# Cell_Voltage_Sensing.net
KiCad netlist of a schematic drawn in Altium Designer
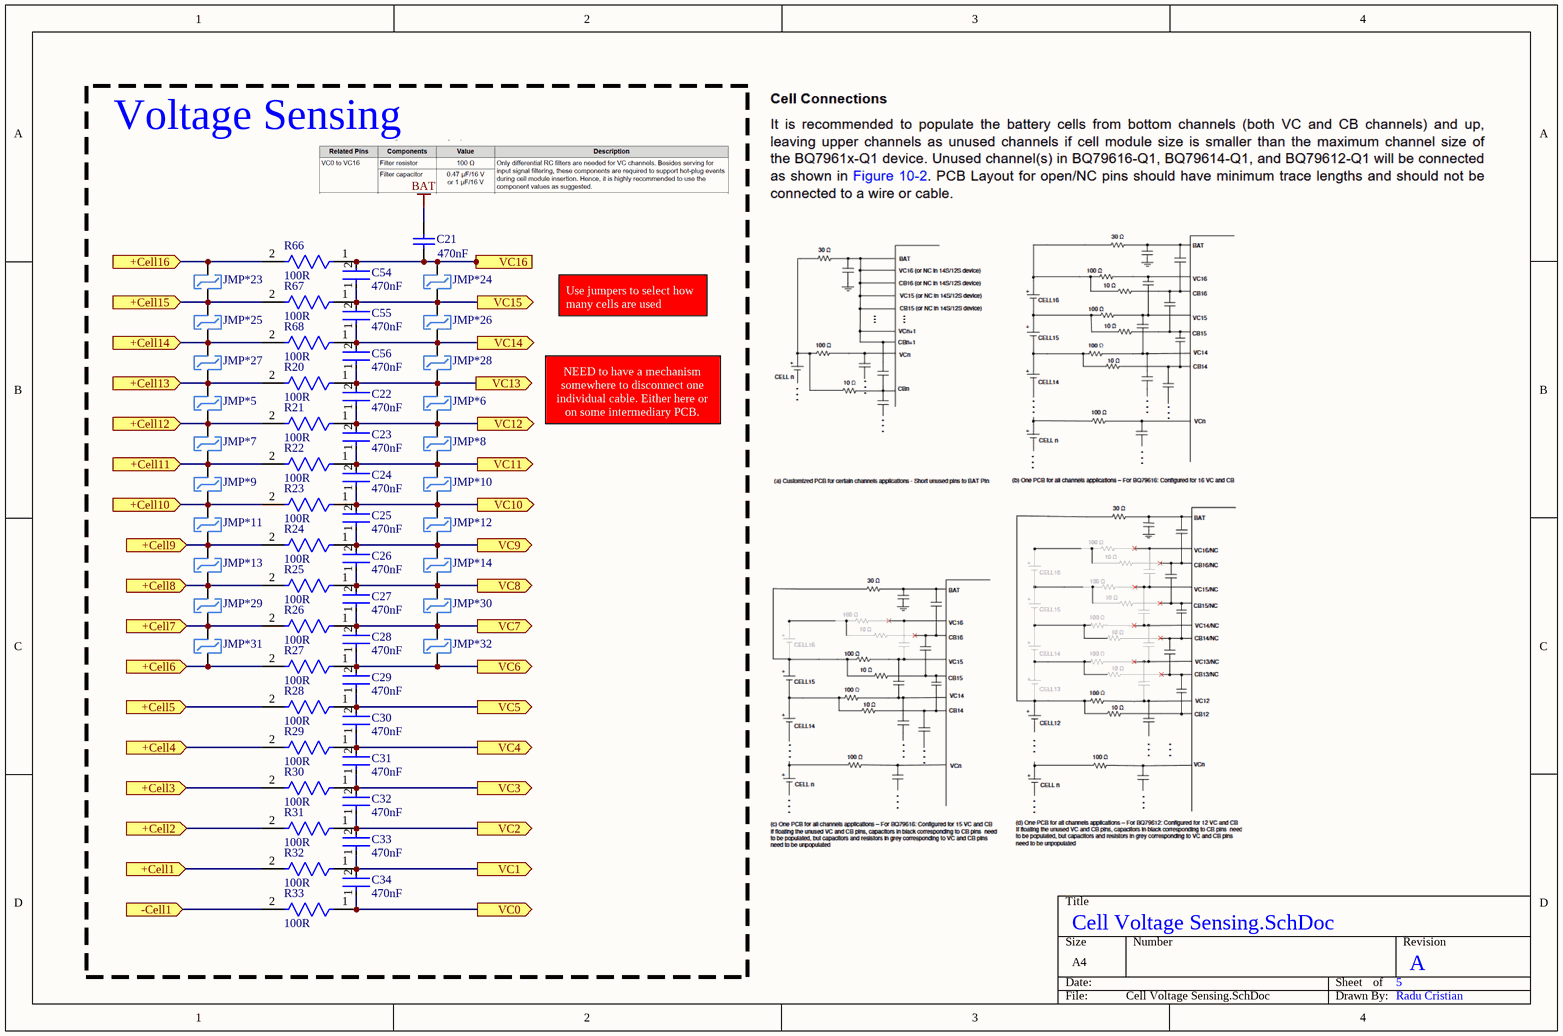
[diagram p0: Cell Voltage Sensing.SchDoc]

(export (version "E")
  (design (tool "Eeschema 10.0.6"))
  (components
    (comp (ref "C21")
      (value "470nF")
      (footprint "CAPC0603(1608)100_N")
      (description "CAP 470nF 25V ±20% 0603 (1608 Metric) Thickness 1mm SMD")
      (fields (field (name "TOLERANCE") "Â±20%") (field (name "Comment") "CAP 470nF 25V 0603(1608)"))
      (libsource (lib "Altium Content Vault") (part "CAP"))
    )
    (comp (ref "C22")
      (value "08055C474J4Z2A")
      (footprint "FP-0805-L_2_01_0_2-W_1_25-IPC_C")
      (description "Automotive Ceramic Capacitor, 0805, 470nF, 5%, X7R, 15%, 50V")
      (fields (field (name "CAPACITANCE") "470nF") (field (name "TOLERANCE") "5%"))
      (libsource (lib "Altium Content Vault") (part "b4654b650e69147ec39a6b967a45e02"))
    )
    (comp (ref "C23")
      (value "08055C474J4Z2A")
      (footprint "FP-0805-L_2_01_0_2-W_1_25-IPC_C")
      (description "Automotive Ceramic Capacitor, 0805, 470nF, 5%, X7R, 15%, 50V")
      (fields (field (name "CAPACITANCE") "470nF") (field (name "TOLERANCE") "5%"))
      (libsource (lib "Altium Content Vault") (part "b4654b650e69147ec39a6b967a45e02"))
    )
    (comp (ref "C24")
      (value "08055C474J4Z2A")
      (footprint "FP-0805-L_2_01_0_2-W_1_25-IPC_C")
      (description "Automotive Ceramic Capacitor, 0805, 470nF, 5%, X7R, 15%, 50V")
      (fields (field (name "CAPACITANCE") "470nF") (field (name "TOLERANCE") "5%"))
      (libsource (lib "Altium Content Vault") (part "b4654b650e69147ec39a6b967a45e02"))
    )
    (comp (ref "C25")
      (value "08055C474J4Z2A")
      (footprint "FP-0805-L_2_01_0_2-W_1_25-IPC_C")
      (description "Automotive Ceramic Capacitor, 0805, 470nF, 5%, X7R, 15%, 50V")
      (fields (field (name "CAPACITANCE") "470nF") (field (name "TOLERANCE") "5%"))
      (libsource (lib "Altium Content Vault") (part "b4654b650e69147ec39a6b967a45e02"))
    )
    (comp (ref "C26")
      (value "08055C474J4Z2A")
      (footprint "FP-0805-L_2_01_0_2-W_1_25-IPC_C")
      (description "Automotive Ceramic Capacitor, 0805, 470nF, 5%, X7R, 15%, 50V")
      (fields (field (name "CAPACITANCE") "470nF") (field (name "TOLERANCE") "5%"))
      (libsource (lib "Altium Content Vault") (part "b4654b650e69147ec39a6b967a45e02"))
    )
    (comp (ref "C27")
      (value "08055C474J4Z2A")
      (footprint "FP-0805-L_2_01_0_2-W_1_25-IPC_C")
      (description "Automotive Ceramic Capacitor, 0805, 470nF, 5%, X7R, 15%, 50V")
      (fields (field (name "CAPACITANCE") "470nF") (field (name "TOLERANCE") "5%"))
      (libsource (lib "Altium Content Vault") (part "b4654b650e69147ec39a6b967a45e02"))
    )
    (comp (ref "C28")
      (value "08055C474J4Z2A")
      (footprint "FP-0805-L_2_01_0_2-W_1_25-IPC_C")
      (description "Automotive Ceramic Capacitor, 0805, 470nF, 5%, X7R, 15%, 50V")
      (fields (field (name "CAPACITANCE") "470nF") (field (name "TOLERANCE") "5%"))
      (libsource (lib "Altium Content Vault") (part "b4654b650e69147ec39a6b967a45e02"))
    )
    (comp (ref "C29")
      (value "08055C474J4Z2A")
      (footprint "FP-0805-L_2_01_0_2-W_1_25-IPC_C")
      (description "Automotive Ceramic Capacitor, 0805, 470nF, 5%, X7R, 15%, 50V")
      (fields (field (name "CAPACITANCE") "470nF") (field (name "TOLERANCE") "5%"))
      (libsource (lib "Altium Content Vault") (part "b4654b650e69147ec39a6b967a45e02"))
    )
    (comp (ref "C30")
      (value "08055C474J4Z2A")
      (footprint "FP-0805-L_2_01_0_2-W_1_25-IPC_C")
      (description "Automotive Ceramic Capacitor, 0805, 470nF, 5%, X7R, 15%, 50V")
      (fields (field (name "CAPACITANCE") "470nF") (field (name "TOLERANCE") "5%"))
      (libsource (lib "Altium Content Vault") (part "b4654b650e69147ec39a6b967a45e02"))
    )
    (comp (ref "C31")
      (value "08055C474J4Z2A")
      (footprint "FP-0805-L_2_01_0_2-W_1_25-IPC_C")
      (description "Automotive Ceramic Capacitor, 0805, 470nF, 5%, X7R, 15%, 50V")
      (fields (field (name "CAPACITANCE") "470nF") (field (name "TOLERANCE") "5%"))
      (libsource (lib "Altium Content Vault") (part "b4654b650e69147ec39a6b967a45e02"))
    )
    (comp (ref "C32")
      (value "08055C474J4Z2A")
      (footprint "FP-0805-L_2_01_0_2-W_1_25-IPC_C")
      (description "Automotive Ceramic Capacitor, 0805, 470nF, 5%, X7R, 15%, 50V")
      (fields (field (name "CAPACITANCE") "470nF") (field (name "TOLERANCE") "5%"))
      (libsource (lib "Altium Content Vault") (part "b4654b650e69147ec39a6b967a45e02"))
    )
    (comp (ref "C33")
      (value "08055C474J4Z2A")
      (footprint "FP-0805-L_2_01_0_2-W_1_25-IPC_C")
      (description "Automotive Ceramic Capacitor, 0805, 470nF, 5%, X7R, 15%, 50V")
      (fields (field (name "CAPACITANCE") "470nF") (field (name "TOLERANCE") "5%"))
      (libsource (lib "Altium Content Vault") (part "b4654b650e69147ec39a6b967a45e02"))
    )
    (comp (ref "C34")
      (value "08055C474J4Z2A")
      (footprint "FP-0805-L_2_01_0_2-W_1_25-IPC_C")
      (description "Automotive Ceramic Capacitor, 0805, 470nF, 5%, X7R, 15%, 50V")
      (fields (field (name "CAPACITANCE") "470nF") (field (name "TOLERANCE") "5%"))
      (libsource (lib "Altium Content Vault") (part "b4654b650e69147ec39a6b967a45e02"))
    )
    (comp (ref "C54")
      (value "08055C474J4Z2A")
      (footprint "FP-0805-L_2_01_0_2-W_1_25-IPC_C")
      (description "Automotive Ceramic Capacitor, 0805, 470nF, 5%, X7R, 15%, 50V")
      (fields (field (name "CAPACITANCE") "470nF") (field (name "TOLERANCE") "5%"))
      (libsource (lib "Altium Content Vault") (part "b4654b650e69147ec39a6b967a45e02"))
    )
    (comp (ref "C55")
      (value "08055C474J4Z2A")
      (footprint "FP-0805-L_2_01_0_2-W_1_25-IPC_C")
      (description "Automotive Ceramic Capacitor, 0805, 470nF, 5%, X7R, 15%, 50V")
      (fields (field (name "CAPACITANCE") "470nF") (field (name "TOLERANCE") "5%"))
      (libsource (lib "Altium Content Vault") (part "b4654b650e69147ec39a6b967a45e02"))
    )
    (comp (ref "C56")
      (value "08055C474J4Z2A")
      (footprint "FP-0805-L_2_01_0_2-W_1_25-IPC_C")
      (description "Automotive Ceramic Capacitor, 0805, 470nF, 5%, X7R, 15%, 50V")
      (fields (field (name "CAPACITANCE") "470nF") (field (name "TOLERANCE") "5%"))
      (libsource (lib "Altium Content Vault") (part "b4654b650e69147ec39a6b967a45e02"))
    )
    (comp (ref "JMP*5")
      (value "Solder Jumper")
      (footprint "Solder Jumper-Footprint-1")
      (description "2 port solder jumper")
      (libsource (lib "goulash den") (part "Jumper"))
    )
    (comp (ref "JMP*6")
      (value "Solder Jumper")
      (footprint "Solder Jumper-Footprint-1")
      (description "2 port solder jumper")
      (libsource (lib "goulash den") (part "Jumper"))
    )
    (comp (ref "JMP*7")
      (value "Solder Jumper")
      (footprint "Solder Jumper-Footprint-1")
      (description "2 port solder jumper")
      (libsource (lib "goulash den") (part "Jumper"))
    )
    (comp (ref "JMP*8")
      (value "Solder Jumper")
      (footprint "Solder Jumper-Footprint-1")
      (description "2 port solder jumper")
      (libsource (lib "goulash den") (part "Jumper"))
    )
    (comp (ref "JMP*9")
      (value "Solder Jumper")
      (footprint "Solder Jumper-Footprint-1")
      (description "2 port solder jumper")
      (libsource (lib "goulash den") (part "Jumper"))
    )
    (comp (ref "JMP*10")
      (value "Solder Jumper")
      (footprint "Solder Jumper-Footprint-1")
      (description "2 port solder jumper")
      (libsource (lib "goulash den") (part "Jumper"))
    )
    (comp (ref "JMP*11")
      (value "Solder Jumper")
      (footprint "Solder Jumper-Footprint-1")
      (description "2 port solder jumper")
      (libsource (lib "goulash den") (part "Jumper"))
    )
    (comp (ref "JMP*12")
      (value "Solder Jumper")
      (footprint "Solder Jumper-Footprint-1")
      (description "2 port solder jumper")
      (libsource (lib "goulash den") (part "Jumper"))
    )
    (comp (ref "JMP*13")
      (value "Solder Jumper")
      (footprint "Solder Jumper-Footprint-1")
      (description "2 port solder jumper")
      (libsource (lib "goulash den") (part "Jumper"))
    )
    (comp (ref "JMP*14")
      (value "Solder Jumper")
      (footprint "Solder Jumper-Footprint-1")
      (description "2 port solder jumper")
      (libsource (lib "goulash den") (part "Jumper"))
    )
    (comp (ref "JMP*23")
      (value "Solder Jumper")
      (footprint "Solder Jumper-Footprint-1")
      (description "2 port solder jumper")
      (libsource (lib "goulash den") (part "Jumper"))
    )
    (comp (ref "JMP*24")
      (value "Solder Jumper")
      (footprint "Solder Jumper-Footprint-1")
      (description "2 port solder jumper")
      (libsource (lib "goulash den") (part "Jumper"))
    )
    (comp (ref "JMP*25")
      (value "Solder Jumper")
      (footprint "Solder Jumper-Footprint-1")
      (description "2 port solder jumper")
      (libsource (lib "goulash den") (part "Jumper"))
    )
    (comp (ref "JMP*26")
      (value "Solder Jumper")
      (footprint "Solder Jumper-Footprint-1")
      (description "2 port solder jumper")
      (libsource (lib "goulash den") (part "Jumper"))
    )
    (comp (ref "JMP*27")
      (value "Solder Jumper")
      (footprint "Solder Jumper-Footprint-1")
      (description "2 port solder jumper")
      (libsource (lib "goulash den") (part "Jumper"))
    )
    (comp (ref "JMP*28")
      (value "Solder Jumper")
      (footprint "Solder Jumper-Footprint-1")
      (description "2 port solder jumper")
      (libsource (lib "goulash den") (part "Jumper"))
    )
    (comp (ref "JMP*29")
      (value "Solder Jumper")
      (footprint "Solder Jumper-Footprint-1")
      (description "2 port solder jumper")
      (libsource (lib "goulash den") (part "Jumper"))
    )
    (comp (ref "JMP*30")
      (value "Solder Jumper")
      (footprint "Solder Jumper-Footprint-1")
      (description "2 port solder jumper")
      (libsource (lib "goulash den") (part "Jumper"))
    )
    (comp (ref "JMP*31")
      (value "Solder Jumper")
      (footprint "Solder Jumper-Footprint-1")
      (description "2 port solder jumper")
      (libsource (lib "goulash den") (part "Jumper"))
    )
    (comp (ref "JMP*32")
      (value "Solder Jumper")
      (footprint "Solder Jumper-Footprint-1")
      (description "2 port solder jumper")
      (libsource (lib "goulash den") (part "Jumper"))
    )
    (comp (ref "R20")
      (value "CRCW0603100RFHEAP")
      (footprint "FP-CRCW0603-Pe3-MFG")
      (description "RES Thick Film, 100Ω, 1%, 0.1W, 50ppm/°C, 0603")
      (fields (field (name "RESISTANCE") "100R") (field (name "TOLERANCE") "1%"))
      (libsource (lib "Altium Content Vault") (part "1029c3af85768c4190bb7ad29bc67b5"))
    )
    (comp (ref "R21")
      (value "CRCW0603100RFHEAP")
      (footprint "FP-CRCW0603-Pe3-MFG")
      (description "RES Thick Film, 100Ω, 1%, 0.1W, 50ppm/°C, 0603")
      (fields (field (name "RESISTANCE") "100R") (field (name "TOLERANCE") "1%"))
      (libsource (lib "Altium Content Vault") (part "1029c3af85768c4190bb7ad29bc67b5"))
    )
    (comp (ref "R22")
      (value "CRCW0603100RFHEAP")
      (footprint "FP-CRCW0603-Pe3-MFG")
      (description "RES Thick Film, 100Ω, 1%, 0.1W, 50ppm/°C, 0603")
      (fields (field (name "RESISTANCE") "100R") (field (name "TOLERANCE") "1%"))
      (libsource (lib "Altium Content Vault") (part "1029c3af85768c4190bb7ad29bc67b5"))
    )
    (comp (ref "R23")
      (value "CRCW0603100RFHEAP")
      (footprint "FP-CRCW0603-Pe3-MFG")
      (description "RES Thick Film, 100Ω, 1%, 0.1W, 50ppm/°C, 0603")
      (fields (field (name "RESISTANCE") "100R") (field (name "TOLERANCE") "1%"))
      (libsource (lib "Altium Content Vault") (part "1029c3af85768c4190bb7ad29bc67b5"))
    )
    (comp (ref "R24")
      (value "CRCW0603100RFHEAP")
      (footprint "FP-CRCW0603-Pe3-MFG")
      (description "RES Thick Film, 100Ω, 1%, 0.1W, 50ppm/°C, 0603")
      (fields (field (name "RESISTANCE") "100R") (field (name "TOLERANCE") "1%"))
      (libsource (lib "Altium Content Vault") (part "1029c3af85768c4190bb7ad29bc67b5"))
    )
    (comp (ref "R25")
      (value "CRCW0603100RFHEAP")
      (footprint "FP-CRCW0603-Pe3-MFG")
      (description "RES Thick Film, 100Ω, 1%, 0.1W, 50ppm/°C, 0603")
      (fields (field (name "RESISTANCE") "100R") (field (name "TOLERANCE") "1%"))
      (libsource (lib "Altium Content Vault") (part "1029c3af85768c4190bb7ad29bc67b5"))
    )
    (comp (ref "R26")
      (value "CRCW0603100RFHEAP")
      (footprint "FP-CRCW0603-Pe3-MFG")
      (description "RES Thick Film, 100Ω, 1%, 0.1W, 50ppm/°C, 0603")
      (fields (field (name "RESISTANCE") "100R") (field (name "TOLERANCE") "1%"))
      (libsource (lib "Altium Content Vault") (part "1029c3af85768c4190bb7ad29bc67b5"))
    )
    (comp (ref "R27")
      (value "CRCW0603100RFHEAP")
      (footprint "FP-CRCW0603-Pe3-MFG")
      (description "RES Thick Film, 100Ω, 1%, 0.1W, 50ppm/°C, 0603")
      (fields (field (name "RESISTANCE") "100R") (field (name "TOLERANCE") "1%"))
      (libsource (lib "Altium Content Vault") (part "1029c3af85768c4190bb7ad29bc67b5"))
    )
    (comp (ref "R28")
      (value "CRCW0603100RFHEAP")
      (footprint "FP-CRCW0603-Pe3-MFG")
      (description "RES Thick Film, 100Ω, 1%, 0.1W, 50ppm/°C, 0603")
      (fields (field (name "RESISTANCE") "100R") (field (name "TOLERANCE") "1%"))
      (libsource (lib "Altium Content Vault") (part "1029c3af85768c4190bb7ad29bc67b5"))
    )
    (comp (ref "R29")
      (value "CRCW0603100RFHEAP")
      (footprint "FP-CRCW0603-Pe3-MFG")
      (description "RES Thick Film, 100Ω, 1%, 0.1W, 50ppm/°C, 0603")
      (fields (field (name "RESISTANCE") "100R") (field (name "TOLERANCE") "1%"))
      (libsource (lib "Altium Content Vault") (part "1029c3af85768c4190bb7ad29bc67b5"))
    )
    (comp (ref "R30")
      (value "CRCW0603100RFHEAP")
      (footprint "FP-CRCW0603-Pe3-MFG")
      (description "RES Thick Film, 100Ω, 1%, 0.1W, 50ppm/°C, 0603")
      (fields (field (name "RESISTANCE") "100R") (field (name "TOLERANCE") "1%"))
      (libsource (lib "Altium Content Vault") (part "1029c3af85768c4190bb7ad29bc67b5"))
    )
    (comp (ref "R31")
      (value "CRCW0603100RFHEAP")
      (footprint "FP-CRCW0603-Pe3-MFG")
      (description "RES Thick Film, 100Ω, 1%, 0.1W, 50ppm/°C, 0603")
      (fields (field (name "RESISTANCE") "100R") (field (name "TOLERANCE") "1%"))
      (libsource (lib "Altium Content Vault") (part "1029c3af85768c4190bb7ad29bc67b5"))
    )
    (comp (ref "R32")
      (value "CRCW0603100RFHEAP")
      (footprint "FP-CRCW0603-Pe3-MFG")
      (description "RES Thick Film, 100Ω, 1%, 0.1W, 50ppm/°C, 0603")
      (fields (field (name "RESISTANCE") "100R") (field (name "TOLERANCE") "1%"))
      (libsource (lib "Altium Content Vault") (part "1029c3af85768c4190bb7ad29bc67b5"))
    )
    (comp (ref "R33")
      (value "CRCW0603100RFHEAP")
      (footprint "FP-CRCW0603-Pe3-MFG")
      (description "RES Thick Film, 100Ω, 1%, 0.1W, 50ppm/°C, 0603")
      (fields (field (name "RESISTANCE") "100R") (field (name "TOLERANCE") "1%"))
      (libsource (lib "Altium Content Vault") (part "1029c3af85768c4190bb7ad29bc67b5"))
    )
    (comp (ref "R66")
      (value "CRCW0603100RFHEAP")
      (footprint "FP-CRCW0603-Pe3-MFG")
      (description "RES Thick Film, 100Ω, 1%, 0.1W, 50ppm/°C, 0603")
      (fields (field (name "RESISTANCE") "100R") (field (name "TOLERANCE") "1%"))
      (libsource (lib "Altium Content Vault") (part "1029c3af85768c4190bb7ad29bc67b5"))
    )
    (comp (ref "R67")
      (value "CRCW0603100RFHEAP")
      (footprint "FP-CRCW0603-Pe3-MFG")
      (description "RES Thick Film, 100Ω, 1%, 0.1W, 50ppm/°C, 0603")
      (fields (field (name "RESISTANCE") "100R") (field (name "TOLERANCE") "1%"))
      (libsource (lib "Altium Content Vault") (part "1029c3af85768c4190bb7ad29bc67b5"))
    )
    (comp (ref "R68")
      (value "CRCW0603100RFHEAP")
      (footprint "FP-CRCW0603-Pe3-MFG")
      (description "RES Thick Film, 100Ω, 1%, 0.1W, 50ppm/°C, 0603")
      (fields (field (name "RESISTANCE") "100R") (field (name "TOLERANCE") "1%"))
      (libsource (lib "Altium Content Vault") (part "1029c3af85768c4190bb7ad29bc67b5"))
    )
  )
  (nets
    (net (code "1") (name "/+Cell1") (class "Default")
      (node (ref "R32") (pin "2") (pinfunction "2_2") (pintype "passive"))
    )
    (net (code "2") (name "/+Cell2") (class "Default")
      (node (ref "R31") (pin "2") (pinfunction "2_2") (pintype "passive"))
    )
    (net (code "3") (name "/+Cell3") (class "Default")
      (node (ref "R30") (pin "2") (pinfunction "2_2") (pintype "passive"))
    )
    (net (code "4") (name "/+Cell4") (class "Default")
      (node (ref "R29") (pin "2") (pinfunction "2_2") (pintype "passive"))
    )
    (net (code "5") (name "/+Cell5") (class "Default")
      (node (ref "R28") (pin "2") (pinfunction "2_2") (pintype "passive"))
    )
    (net (code "6") (name "/+Cell6") (class "Default")
      (node (ref "JMP*31") (pin "1") (pinfunction "1_1") (pintype "passive"))
      (node (ref "R27") (pin "2") (pinfunction "2_2") (pintype "passive"))
    )
    (net (code "7") (name "/+Cell7") (class "Default")
      (node (ref "JMP*29") (pin "1") (pinfunction "1_1") (pintype "passive"))
      (node (ref "JMP*31") (pin "2") (pinfunction "2_2") (pintype "passive"))
      (node (ref "R26") (pin "2") (pinfunction "2_2") (pintype "passive"))
    )
    (net (code "8") (name "/+Cell8") (class "Default")
      (node (ref "JMP*13") (pin "1") (pinfunction "1_1") (pintype "passive"))
      (node (ref "JMP*29") (pin "2") (pinfunction "2_2") (pintype "passive"))
      (node (ref "R25") (pin "2") (pinfunction "2_2") (pintype "passive"))
    )
    (net (code "9") (name "/+Cell9") (class "Default")
      (node (ref "JMP*11") (pin "1") (pinfunction "1_1") (pintype "passive"))
      (node (ref "JMP*13") (pin "2") (pinfunction "2_2") (pintype "passive"))
      (node (ref "R24") (pin "2") (pinfunction "2_2") (pintype "passive"))
    )
    (net (code "10") (name "/+Cell10") (class "Default")
      (node (ref "JMP*11") (pin "2") (pinfunction "2_2") (pintype "passive"))
      (node (ref "JMP*9") (pin "1") (pinfunction "1_1") (pintype "passive"))
      (node (ref "R23") (pin "2") (pinfunction "2_2") (pintype "passive"))
    )
    (net (code "11") (name "/+Cell11") (class "Default")
      (node (ref "JMP*7") (pin "1") (pinfunction "1_1") (pintype "passive"))
      (node (ref "JMP*9") (pin "2") (pinfunction "2_2") (pintype "passive"))
      (node (ref "R22") (pin "2") (pinfunction "2_2") (pintype "passive"))
    )
    (net (code "12") (name "/+Cell12") (class "Default")
      (node (ref "JMP*5") (pin "1") (pinfunction "1_1") (pintype "passive"))
      (node (ref "JMP*7") (pin "2") (pinfunction "2_2") (pintype "passive"))
      (node (ref "R21") (pin "2") (pinfunction "2_2") (pintype "passive"))
    )
    (net (code "13") (name "/+Cell13") (class "Default")
      (node (ref "JMP*27") (pin "1") (pinfunction "1_1") (pintype "passive"))
      (node (ref "JMP*5") (pin "2") (pinfunction "2_2") (pintype "passive"))
      (node (ref "R20") (pin "2") (pinfunction "2_2") (pintype "passive"))
    )
    (net (code "14") (name "/+Cell14") (class "Default")
      (node (ref "JMP*25") (pin "1") (pinfunction "1_1") (pintype "passive"))
      (node (ref "JMP*27") (pin "2") (pinfunction "2_2") (pintype "passive"))
      (node (ref "R68") (pin "2") (pinfunction "2_2") (pintype "passive"))
    )
    (net (code "15") (name "/+Cell15") (class "Default")
      (node (ref "JMP*23") (pin "1") (pinfunction "1_1") (pintype "passive"))
      (node (ref "JMP*25") (pin "2") (pinfunction "2_2") (pintype "passive"))
      (node (ref "R67") (pin "2") (pinfunction "2_2") (pintype "passive"))
    )
    (net (code "16") (name "/+Cell16") (class "Default")
      (node (ref "JMP*23") (pin "2") (pinfunction "2_2") (pintype "passive"))
      (node (ref "R66") (pin "2") (pinfunction "2_2") (pintype "passive"))
    )
    (net (code "17") (name "/-Cell1") (class "Default")
      (node (ref "R33") (pin "2") (pinfunction "2_2") (pintype "passive"))
    )
    (net (code "18") (name "/VC0") (class "Default")
      (node (ref "C34") (pin "1") (pinfunction "1_1") (pintype "passive"))
      (node (ref "R33") (pin "1") (pinfunction "1_1") (pintype "passive"))
    )
    (net (code "19") (name "/VC1") (class "Default")
      (node (ref "C33") (pin "1") (pinfunction "1_1") (pintype "passive"))
      (node (ref "C34") (pin "2") (pinfunction "2_2") (pintype "passive"))
      (node (ref "R32") (pin "1") (pinfunction "1_1") (pintype "passive"))
    )
    (net (code "20") (name "/VC2") (class "Default")
      (node (ref "C32") (pin "1") (pinfunction "1_1") (pintype "passive"))
      (node (ref "C33") (pin "2") (pinfunction "2_2") (pintype "passive"))
      (node (ref "R31") (pin "1") (pinfunction "1_1") (pintype "passive"))
    )
    (net (code "21") (name "/VC3") (class "Default")
      (node (ref "C31") (pin "1") (pinfunction "1_1") (pintype "passive"))
      (node (ref "C32") (pin "2") (pinfunction "2_2") (pintype "passive"))
      (node (ref "R30") (pin "1") (pinfunction "1_1") (pintype "passive"))
    )
    (net (code "22") (name "/VC4") (class "Default")
      (node (ref "C30") (pin "1") (pinfunction "1_1") (pintype "passive"))
      (node (ref "C31") (pin "2") (pinfunction "2_2") (pintype "passive"))
      (node (ref "R29") (pin "1") (pinfunction "1_1") (pintype "passive"))
    )
    (net (code "23") (name "/VC5") (class "Default")
      (node (ref "C29") (pin "1") (pinfunction "1_1") (pintype "passive"))
      (node (ref "C30") (pin "2") (pinfunction "2_2") (pintype "passive"))
      (node (ref "R28") (pin "1") (pinfunction "1_1") (pintype "passive"))
    )
    (net (code "24") (name "/VC6") (class "Default")
      (node (ref "C28") (pin "1") (pinfunction "1_1") (pintype "passive"))
      (node (ref "C29") (pin "2") (pinfunction "2_2") (pintype "passive"))
      (node (ref "JMP*32") (pin "1") (pinfunction "1_1") (pintype "passive"))
      (node (ref "R27") (pin "1") (pinfunction "1_1") (pintype "passive"))
    )
    (net (code "25") (name "/VC7") (class "Default")
      (node (ref "C27") (pin "1") (pinfunction "1_1") (pintype "passive"))
      (node (ref "C28") (pin "2") (pinfunction "2_2") (pintype "passive"))
      (node (ref "JMP*30") (pin "1") (pinfunction "1_1") (pintype "passive"))
      (node (ref "JMP*32") (pin "2") (pinfunction "2_2") (pintype "passive"))
      (node (ref "R26") (pin "1") (pinfunction "1_1") (pintype "passive"))
    )
    (net (code "26") (name "/VC8") (class "Default")
      (node (ref "C26") (pin "1") (pinfunction "1_1") (pintype "passive"))
      (node (ref "C27") (pin "2") (pinfunction "2_2") (pintype "passive"))
      (node (ref "JMP*14") (pin "1") (pinfunction "1_1") (pintype "passive"))
      (node (ref "JMP*30") (pin "2") (pinfunction "2_2") (pintype "passive"))
      (node (ref "R25") (pin "1") (pinfunction "1_1") (pintype "passive"))
    )
    (net (code "27") (name "/VC9") (class "Default")
      (node (ref "C25") (pin "1") (pinfunction "1_1") (pintype "passive"))
      (node (ref "C26") (pin "2") (pinfunction "2_2") (pintype "passive"))
      (node (ref "JMP*12") (pin "1") (pinfunction "1_1") (pintype "passive"))
      (node (ref "JMP*14") (pin "2") (pinfunction "2_2") (pintype "passive"))
      (node (ref "R24") (pin "1") (pinfunction "1_1") (pintype "passive"))
    )
    (net (code "28") (name "/VC10") (class "Default")
      (node (ref "C24") (pin "1") (pinfunction "1_1") (pintype "passive"))
      (node (ref "C25") (pin "2") (pinfunction "2_2") (pintype "passive"))
      (node (ref "JMP*10") (pin "1") (pinfunction "1_1") (pintype "passive"))
      (node (ref "JMP*12") (pin "2") (pinfunction "2_2") (pintype "passive"))
      (node (ref "R23") (pin "1") (pinfunction "1_1") (pintype "passive"))
    )
    (net (code "29") (name "/VC11") (class "Default")
      (node (ref "C23") (pin "1") (pinfunction "1_1") (pintype "passive"))
      (node (ref "C24") (pin "2") (pinfunction "2_2") (pintype "passive"))
      (node (ref "JMP*10") (pin "2") (pinfunction "2_2") (pintype "passive"))
      (node (ref "JMP*8") (pin "1") (pinfunction "1_1") (pintype "passive"))
      (node (ref "R22") (pin "1") (pinfunction "1_1") (pintype "passive"))
    )
    (net (code "30") (name "/VC12") (class "Default")
      (node (ref "C22") (pin "1") (pinfunction "1_1") (pintype "passive"))
      (node (ref "C23") (pin "2") (pinfunction "2_2") (pintype "passive"))
      (node (ref "JMP*6") (pin "1") (pinfunction "1_1") (pintype "passive"))
      (node (ref "JMP*8") (pin "2") (pinfunction "2_2") (pintype "passive"))
      (node (ref "R21") (pin "1") (pinfunction "1_1") (pintype "passive"))
    )
    (net (code "31") (name "/VC13") (class "Default")
      (node (ref "C22") (pin "2") (pinfunction "2_2") (pintype "passive"))
      (node (ref "C56") (pin "1") (pinfunction "1_1") (pintype "passive"))
      (node (ref "JMP*28") (pin "1") (pinfunction "1_1") (pintype "passive"))
      (node (ref "JMP*6") (pin "2") (pinfunction "2_2") (pintype "passive"))
      (node (ref "R20") (pin "1") (pinfunction "1_1") (pintype "passive"))
    )
    (net (code "32") (name "/VC14") (class "Default")
      (node (ref "C55") (pin "1") (pinfunction "1_1") (pintype "passive"))
      (node (ref "C56") (pin "2") (pinfunction "2_2") (pintype "passive"))
      (node (ref "JMP*26") (pin "1") (pinfunction "1_1") (pintype "passive"))
      (node (ref "JMP*28") (pin "2") (pinfunction "2_2") (pintype "passive"))
      (node (ref "R68") (pin "1") (pinfunction "1_1") (pintype "passive"))
    )
    (net (code "33") (name "/VC15") (class "Default")
      (node (ref "C54") (pin "1") (pinfunction "1_1") (pintype "passive"))
      (node (ref "C55") (pin "2") (pinfunction "2_2") (pintype "passive"))
      (node (ref "JMP*24") (pin "1") (pinfunction "1_1") (pintype "passive"))
      (node (ref "JMP*26") (pin "2") (pinfunction "2_2") (pintype "passive"))
      (node (ref "R67") (pin "1") (pinfunction "1_1") (pintype "passive"))
    )
    (net (code "34") (name "/VC16") (class "Default")
      (node (ref "C21") (pin "1") (pinfunction "1_1") (pintype "passive"))
      (node (ref "C54") (pin "2") (pinfunction "2_2") (pintype "passive"))
      (node (ref "JMP*24") (pin "2") (pinfunction "2_2") (pintype "passive"))
      (node (ref "R66") (pin "1") (pinfunction "1_1") (pintype "passive"))
    )
    (net (code "35") (name "BAT") (class "Default")
      (node (ref "C21") (pin "2") (pinfunction "2_2") (pintype "passive"))
    )
  )
)
